# Main.net
KiCad netlist of a schematic drawn in Altium Designer
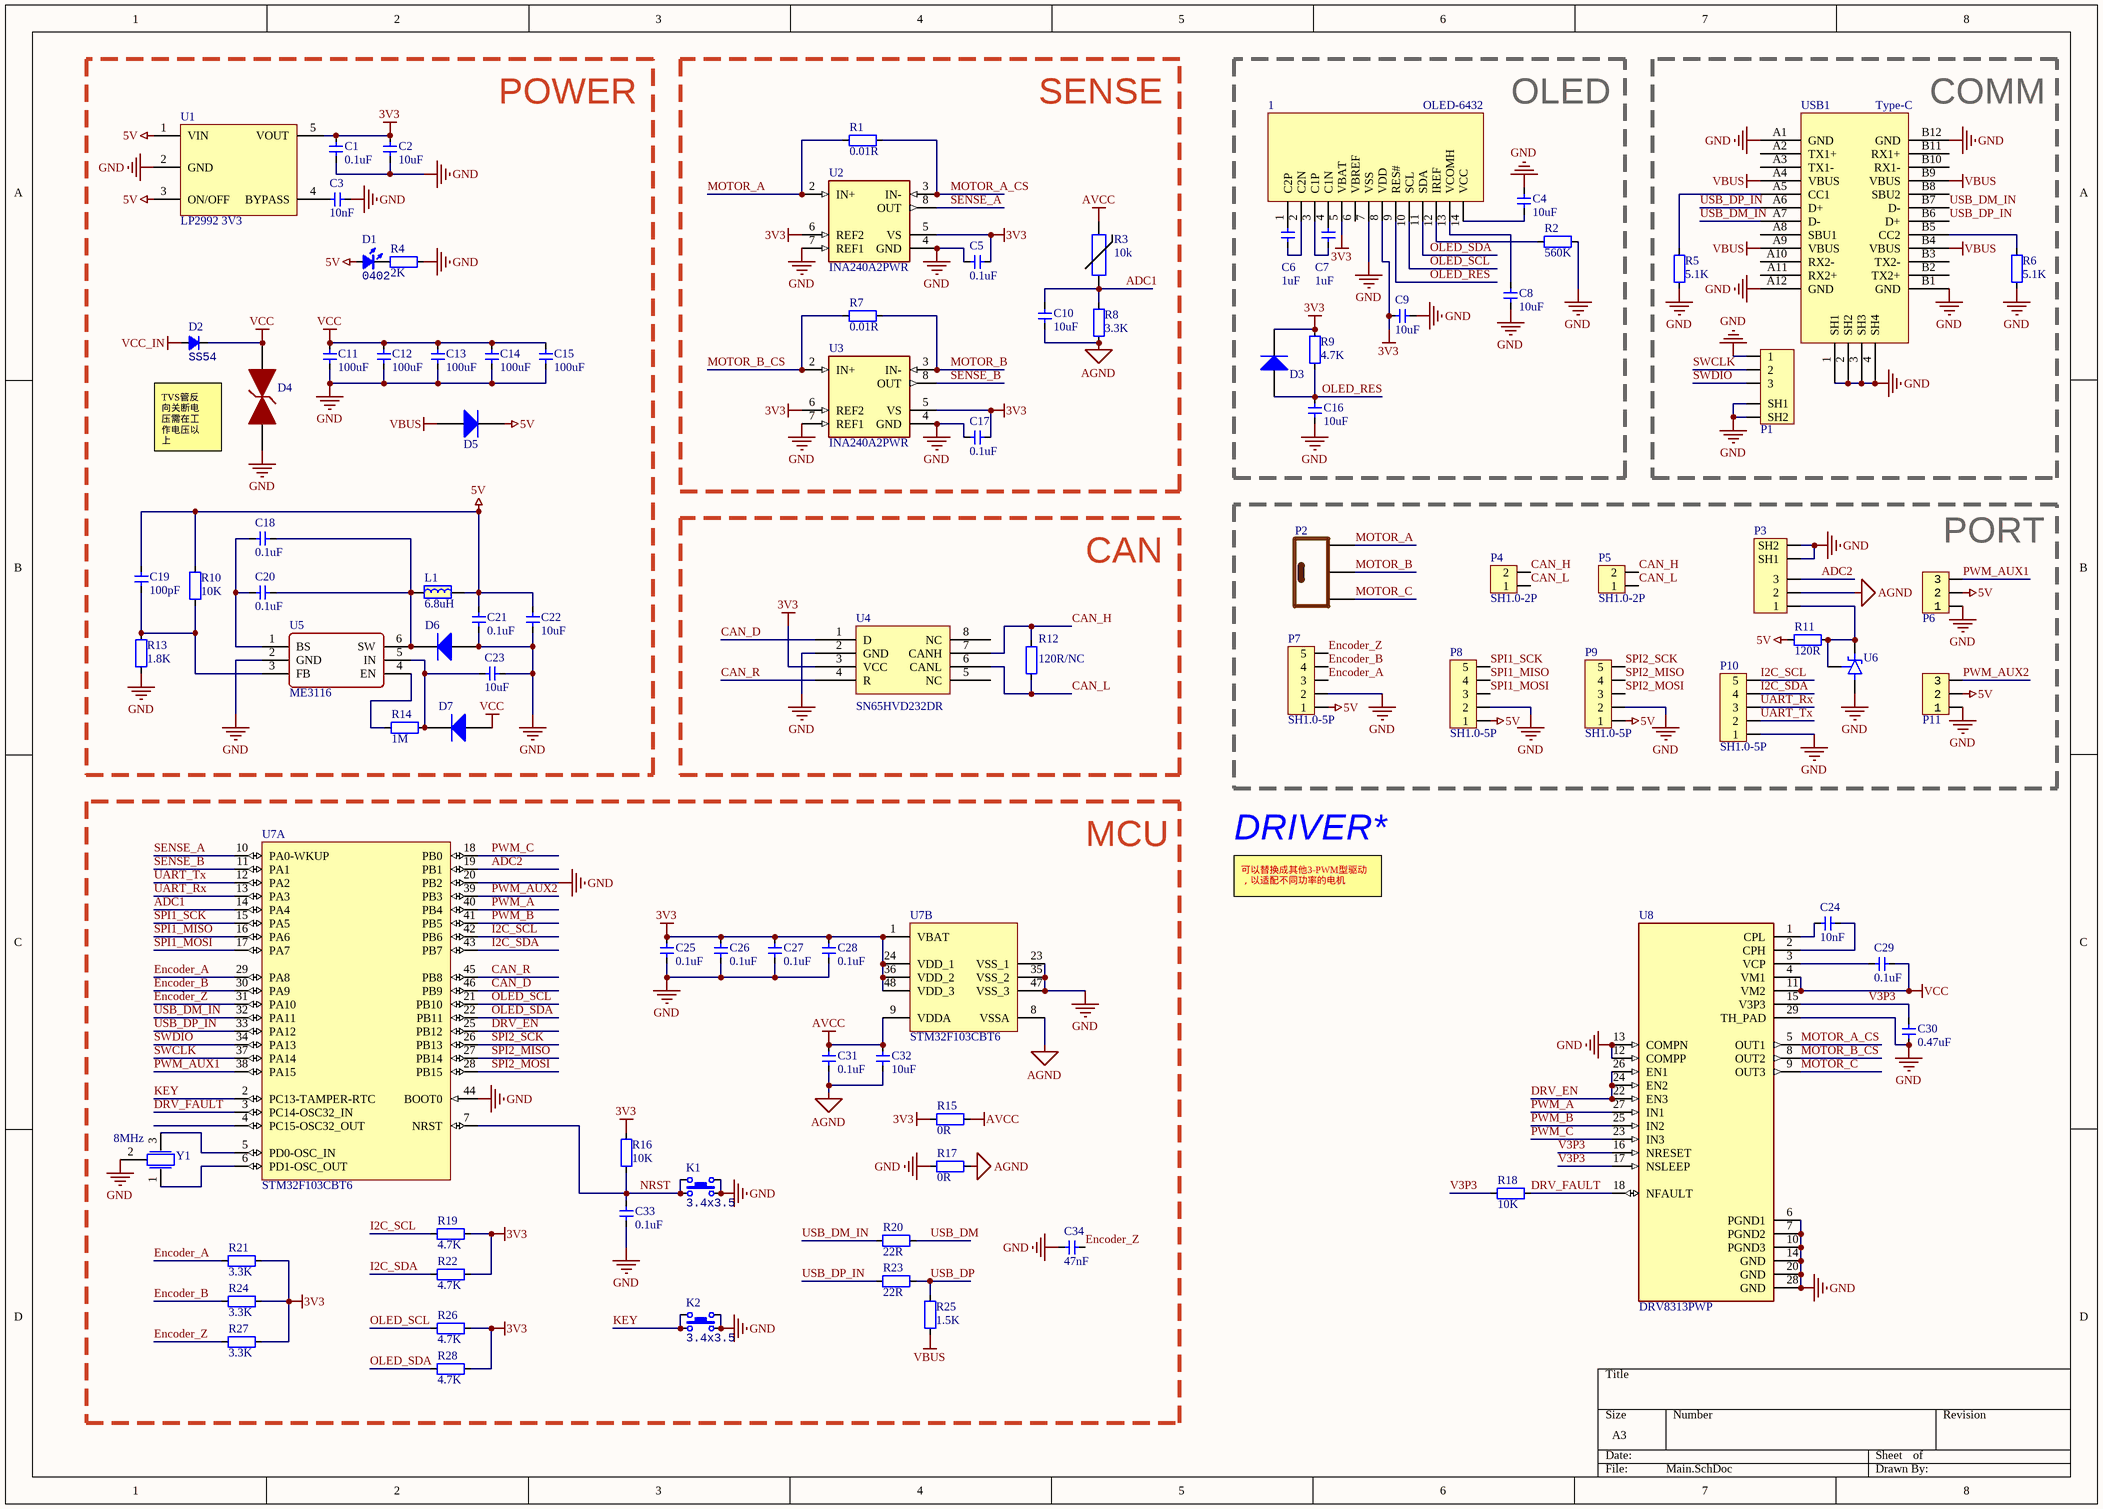
[diagram p0: Main.SchDoc]

(export (version "E")
  (design (tool "Eeschema 10.0.6"))
  (components
    (comp (ref "1")
      (value "OLED-6432")
      (footprint "OLED-6432-TOP")
      (description "显示屏")
      (libsource (lib "mLib") (part "OLED-6432"))
    )
    (comp (ref "C1")
      (value "0.1uF")
      (footprint "CAP_0402")
      (description "Capacitor")
      (libsource (lib "MyPcbLib") (part "电容-0402"))
    )
    (comp (ref "C2")
      (value "10uF")
      (footprint "CAP_0402")
      (description "Capacitor")
      (libsource (lib "MyPcbLib") (part "电容-0402"))
    )
    (comp (ref "C3")
      (value "10nF")
      (footprint "CAP_0402")
      (description "Capacitor")
      (libsource (lib "MyPcbLib") (part "电容-0402"))
    )
    (comp (ref "C4")
      (value "10uF")
      (footprint "CAP_0402")
      (description "Capacitor")
      (libsource (lib "MyPcbLib") (part "电容-0402"))
    )
    (comp (ref "C5")
      (value "0.1uF")
      (footprint "CAP_0402")
      (description "Capacitor")
      (libsource (lib "MyPcbLib") (part "电容-0402"))
    )
    (comp (ref "C6")
      (value "1uF")
      (footprint "CAP_0402")
      (description "Capacitor")
      (libsource (lib "MyPcbLib") (part "电容-0402"))
    )
    (comp (ref "C7")
      (value "1uF")
      (footprint "CAP_0402")
      (description "Capacitor")
      (libsource (lib "MyPcbLib") (part "电容-0402"))
    )
    (comp (ref "C8")
      (value "10uF")
      (footprint "CAP_0402")
      (description "Capacitor")
      (libsource (lib "MyPcbLib") (part "电容-0402"))
    )
    (comp (ref "C9")
      (value "10uF")
      (footprint "CAP_0402")
      (description "Capacitor")
      (libsource (lib "MyPcbLib") (part "电容-0402"))
    )
    (comp (ref "C10")
      (value "10uF")
      (footprint "CAP_0402")
      (description "Capacitor")
      (libsource (lib "MyPcbLib") (part "电容-0402"))
    )
    (comp (ref "C11")
      (value "100uF")
      (footprint "1206-CAP")
      (description "Capacitor")
      (libsource (lib "MyPcbLib") (part "电容-1206"))
    )
    (comp (ref "C12")
      (value "100uF")
      (footprint "1206-CAP")
      (description "Capacitor")
      (libsource (lib "MyPcbLib") (part "电容-1206"))
    )
    (comp (ref "C13")
      (value "100uF")
      (footprint "1206-CAP")
      (description "Capacitor")
      (libsource (lib "MyPcbLib") (part "电容-1206"))
    )
    (comp (ref "C14")
      (value "100uF")
      (footprint "1206-CAP")
      (description "Capacitor")
      (libsource (lib "MyPcbLib") (part "电容-1206"))
    )
    (comp (ref "C15")
      (value "100uF")
      (footprint "1206-CAP")
      (description "Capacitor")
      (libsource (lib "MyPcbLib") (part "电容-1206"))
    )
    (comp (ref "C16")
      (value "10uF")
      (footprint "CAP_0402")
      (description "Capacitor")
      (libsource (lib "MyPcbLib") (part "电容-0402"))
    )
    (comp (ref "C17")
      (value "0.1uF")
      (footprint "CAP_0402")
      (description "Capacitor")
      (libsource (lib "MyPcbLib") (part "电容-0402"))
    )
    (comp (ref "C18")
      (value "0.1uF")
      (footprint "CAP_0402")
      (description "Capacitor")
      (libsource (lib "MyPcbLib") (part "电容-0402"))
    )
    (comp (ref "C19")
      (value "100pF")
      (footprint "CAP_0402")
      (description "Capacitor")
      (libsource (lib "MyPcbLib") (part "电容-0402"))
    )
    (comp (ref "C20")
      (value "0.1uF")
      (footprint "CAP_0402")
      (description "Capacitor")
      (libsource (lib "MyPcbLib") (part "电容-0402"))
    )
    (comp (ref "C21")
      (value "0.1uF")
      (footprint "CAP_0402")
      (description "Capacitor")
      (libsource (lib "MyPcbLib") (part "电容-0402"))
    )
    (comp (ref "C22")
      (value "10uF")
      (footprint "CAP_0402")
      (description "Capacitor")
      (libsource (lib "MyPcbLib") (part "电容-0402"))
    )
    (comp (ref "C23")
      (value "10uF")
      (footprint "CAP_0402")
      (description "Capacitor")
      (libsource (lib "MyPcbLib") (part "电容-0402"))
    )
    (comp (ref "C24")
      (value "10nF")
      (footprint "CAP_0402")
      (description "Capacitor")
      (libsource (lib "MyPcbLib") (part "电容-0402"))
    )
    (comp (ref "C25")
      (value "0.1uF")
      (footprint "CAP_0402")
      (description "Capacitor")
      (libsource (lib "MyPcbLib") (part "电容-0402"))
    )
    (comp (ref "C26")
      (value "0.1uF")
      (footprint "CAP_0402")
      (description "Capacitor")
      (libsource (lib "MyPcbLib") (part "电容-0402"))
    )
    (comp (ref "C27")
      (value "0.1uF")
      (footprint "CAP_0402")
      (description "Capacitor")
      (libsource (lib "MyPcbLib") (part "电容-0402"))
    )
    (comp (ref "C28")
      (value "0.1uF")
      (footprint "CAP_0402")
      (description "Capacitor")
      (libsource (lib "MyPcbLib") (part "电容-0402"))
    )
    (comp (ref "C29")
      (value "0.1uF")
      (footprint "CAP_0402")
      (description "Capacitor")
      (libsource (lib "MyPcbLib") (part "电容-0402"))
    )
    (comp (ref "C30")
      (value "0.47uF")
      (footprint "CAP_0402")
      (description "Capacitor")
      (libsource (lib "MyPcbLib") (part "电容-0402"))
    )
    (comp (ref "C31")
      (value "0.1uF")
      (footprint "CAP_0402")
      (description "Capacitor")
      (libsource (lib "MyPcbLib") (part "电容-0402"))
    )
    (comp (ref "C32")
      (value "10uF")
      (footprint "CAP_0402")
      (description "Capacitor")
      (libsource (lib "MyPcbLib") (part "电容-0402"))
    )
    (comp (ref "C33")
      (value "0.1uF")
      (footprint "CAP_0402")
      (description "Capacitor")
      (libsource (lib "MyPcbLib") (part "电容-0402"))
    )
    (comp (ref "C34")
      (value "47nF")
      (footprint "CAP_0402")
      (description "Capacitor")
      (libsource (lib "MyPcbLib") (part "电容-0402"))
    )
    (comp (ref "D1")
      (value "color?")
      (footprint "LED_0402_RED")
      (description "LED")
      (fields (field (name "TYPE") "0402"))
      (libsource (lib "KitSprout") (part "LED_0402"))
    )
    (comp (ref "D2")
      (value "SS54")
      (footprint "DO-214AC")
      (description "Diode")
      (libsource (lib "KitSprout") (part "Diode_SMA"))
    )
    (comp (ref "D3")
      (value "二极管-5B5817WS")
      (footprint "SOD-323")
      (description "40V")
      (libsource (lib "MyPcbLib") (part "二极管-5B5817WS"))
    )
    (comp (ref "D4")
      (value "SMBJ28CA")
      (footprint "SMBJ-CA_MFG")
      (libsource (lib "MyPcbLib") (part "SMBJ28CA"))
    )
    (comp (ref "D5")
      (value "二极管-5B5819WS")
      (footprint "SOD-323")
      (description "40V")
      (libsource (lib "MyPcbLib") (part "二极管-5B5817WS"))
    )
    (comp (ref "D6")
      (value "二极管-5B5819WS")
      (footprint "SOD-323")
      (description "40V")
      (libsource (lib "MyPcbLib") (part "二极管-5B5817WS"))
    )
    (comp (ref "D7")
      (value "二极管-5B5819WS")
      (footprint "SOD-323")
      (description "40V")
      (libsource (lib "MyPcbLib") (part "二极管-5B5817WS"))
    )
    (comp (ref "K1")
      (value "3.4x3.5")
      (footprint "ButtonTACT_3.5*3.55_90")
      (description "Button")
      (fields (field (name "Comment") "TACT 4P"))
      (libsource (lib "KitSprout") (part "ButtonTACT"))
    )
    (comp (ref "K2")
      (value "3.4x3.5")
      (footprint "ButtonTACT_3.5*3.55_90")
      (description "Button")
      (fields (field (name "Comment") "TACT 4P"))
      (libsource (lib "KitSprout") (part "ButtonTACT"))
    )
    (comp (ref "L1") (value "6.8uH") (footprint "IND-201612") (libsource (lib "MyPcbLib") (part "电感-201612")))
    (comp (ref "P1")
      (value "SH1.0-3P")
      (footprint "SH1.0-3P")
      (description "Header")
      (libsource (lib "") (part "SH1.0-3P_1"))
    )
    (comp (ref "P2")
      (value "电机接插件-3P")
      (footprint "AMASS-MR30-M")
      (description "AMASS MR30")
      (libsource (lib "MyPcbLib") (part "电机接插件-3P"))
    )
    (comp (ref "P3")
      (value "SH1.0-3P")
      (footprint "SH1.0-3P")
      (description "Header")
      (libsource (lib "MyPcbLib") (part "SH1.0-3P"))
    )
    (comp (ref "P4") (value "SH1.0-2P") (footprint "SH1.0-2P") (libsource (lib "MyPcbLib") (part "SH1.0-2P")))
    (comp (ref "P5") (value "SH1.0-2P") (footprint "SH1.0-2P") (libsource (lib "MyPcbLib") (part "SH1.0-2P")))
    (comp (ref "P6")
      (value "HDR1x3_2.54")
      (footprint "HDR1X3_2.54_180")
      (description "Header")
      (libsource (lib "KitSprout") (part "HDR1x3_2.54"))
    )
    (comp (ref "P7") (value "SH1.0-5P") (footprint "SH1.0-5P") (libsource (lib "MyPcbLib") (part "SH1.0-5P")))
    (comp (ref "P8") (value "SH1.0-5P") (footprint "SH1.0-5P") (libsource (lib "MyPcbLib") (part "SH1.0-5P")))
    (comp (ref "P9") (value "SH1.0-5P") (footprint "SH1.0-5P") (libsource (lib "MyPcbLib") (part "SH1.0-5P")))
    (comp (ref "P10")
      (value "SH1.0-5P")
      (footprint "SH1.0-5P")
      (libsource (lib "MyPcbLib") (part "SH1.0-5P"))
    )
    (comp (ref "P11")
      (value "HDR1x3_2.54")
      (footprint "HDR1X3_2.54_180")
      (description "Header")
      (libsource (lib "KitSprout") (part "HDR1x3_2.54"))
    )
    (comp (ref "R1")
      (value "0.01R")
      (footprint "1206-RES")
      (description "Resistor")
      (libsource (lib "MyPcbLib") (part "电阻-1206"))
    )
    (comp (ref "R2")
      (value "560K")
      (footprint "RES_0402")
      (description "Resistor")
      (libsource (lib "") (part "电阻-0402_2"))
    )
    (comp (ref "R3")
      (value "10k")
      (footprint "RES_0402")
      (description "THERMISTOR 10K OHM NTC 0402 SMD")
      (fields (field (name "Comment") "NCP15XH103F03RC"))
      (libsource (lib "MyPcbLib") (part "NCP15XH103F03RC"))
    )
    (comp (ref "R4")
      (value "2K")
      (footprint "RES_0402")
      (description "Resistor")
      (libsource (lib "") (part "电阻-0402_2"))
    )
    (comp (ref "R5")
      (value "5.1K")
      (footprint "RES_0402")
      (description "Resistor")
      (libsource (lib "") (part "电阻-0402_3"))
    )
    (comp (ref "R6")
      (value "5.1K")
      (footprint "RES_0402")
      (description "Resistor")
      (libsource (lib "") (part "电阻-0402_3"))
    )
    (comp (ref "R7")
      (value "0.01R")
      (footprint "1206-RES")
      (description "Resistor")
      (libsource (lib "MyPcbLib") (part "电阻-1206"))
    )
    (comp (ref "R8")
      (value "3.3K")
      (footprint "RES_0402")
      (description "Resistor")
      (libsource (lib "") (part "电阻-0402_1"))
    )
    (comp (ref "R9")
      (value "4.7K")
      (footprint "RES_0402")
      (description "Resistor")
      (libsource (lib "") (part "电阻-0402_3"))
    )
    (comp (ref "R10")
      (value "10K")
      (footprint "RES_0402")
      (description "Resistor")
      (libsource (lib "") (part "电阻-0402_1"))
    )
    (comp (ref "R11")
      (value "120R")
      (footprint "RES_0402")
      (description "Resistor")
      (libsource (lib "MyPcbLib") (part "电阻-0402"))
    )
    (comp (ref "R12")
      (value "120R/NC")
      (footprint "RES_0402")
      (description "Resistor")
      (libsource (lib "") (part "电阻-0402_3"))
    )
    (comp (ref "R13")
      (value "1.8K")
      (footprint "RES_0402")
      (description "Resistor")
      (libsource (lib "") (part "电阻-0402_1"))
    )
    (comp (ref "R14")
      (value "1M")
      (footprint "RES_0402")
      (description "Resistor")
      (libsource (lib "") (part "电阻-0402_2"))
    )
    (comp (ref "R15")
      (value "0R")
      (footprint "RES_0402")
      (description "Resistor")
      (libsource (lib "") (part "电阻-0402_2"))
    )
    (comp (ref "R16")
      (value "10K")
      (footprint "RES_0402")
      (description "Resistor")
      (libsource (lib "") (part "电阻-0402_1"))
    )
    (comp (ref "R17")
      (value "0R")
      (footprint "RES_0402")
      (description "Resistor")
      (libsource (lib "") (part "电阻-0402_2"))
    )
    (comp (ref "R18")
      (value "10K")
      (footprint "RES_0402")
      (description "Resistor")
      (libsource (lib "MyPcbLib") (part "电阻-0402"))
    )
    (comp (ref "R19")
      (value "4.7K")
      (footprint "RES_0402")
      (description "Resistor")
      (libsource (lib "MyPcbLib") (part "电阻-0402"))
    )
    (comp (ref "R20")
      (value "22R")
      (footprint "RES_0402")
      (description "Resistor")
      (libsource (lib "") (part "电阻-0402_2"))
    )
    (comp (ref "R21")
      (value "3.3K")
      (footprint "RES_0402")
      (description "Resistor")
      (libsource (lib "") (part "电阻-0402_2"))
    )
    (comp (ref "R22")
      (value "4.7K")
      (footprint "RES_0402")
      (description "Resistor")
      (libsource (lib "MyPcbLib") (part "电阻-0402"))
    )
    (comp (ref "R23")
      (value "22R")
      (footprint "RES_0402")
      (description "Resistor")
      (libsource (lib "") (part "电阻-0402_2"))
    )
    (comp (ref "R24")
      (value "3.3K")
      (footprint "RES_0402")
      (description "Resistor")
      (libsource (lib "") (part "电阻-0402_2"))
    )
    (comp (ref "R25")
      (value "1.5K")
      (footprint "RES_0402")
      (description "Resistor")
      (libsource (lib "") (part "电阻-0402_3"))
    )
    (comp (ref "R26")
      (value "4.7K")
      (footprint "RES_0402")
      (description "Resistor")
      (libsource (lib "MyPcbLib") (part "电阻-0402"))
    )
    (comp (ref "R27")
      (value "3.3K")
      (footprint "RES_0402")
      (description "Resistor")
      (libsource (lib "") (part "电阻-0402_2"))
    )
    (comp (ref "R28")
      (value "4.7K")
      (footprint "RES_0402")
      (description "Resistor")
      (libsource (lib "MyPcbLib") (part "电阻-0402"))
    )
    (comp (ref "U1")
      (value "LP2992 3V3")
      (footprint "SOT23-5")
      (description "LDO")
      (libsource (lib "MyPcbLib") (part "LP2992"))
    )
    (comp (ref "U2")
      (value "INA240A2PWR")
      (footprint "SOP65 P640X120-8N")
      (fields (field (name "MF") "Texas Instruments"))
      (libsource (lib "mLib") (part "INA240A2PWR"))
    )
    (comp (ref "U3")
      (value "INA240A2PWR")
      (footprint "SOP65 P640X120-8N")
      (fields (field (name "MF") "Texas Instruments"))
      (libsource (lib "mLib") (part "INA240A2PWR"))
    )
    (comp (ref "U4")
      (value "SN65HVD232D")
      (footprint "SO-8")
      (fields
        (field (name "MANUFACTURER") "Texas Instruments")
        (field (name "MANUFACTURER PART NUMBER") "SN65HVD232DR")
      )
      (libsource (lib "MyPcbLib") (part "SN65HVD232D"))
    )
    (comp (ref "U5")
      (value "ME3116")
      (footprint "SOT23-6")
      (description "DC-DC")
      (libsource (lib "MyPcbLib") (part "ME3116"))
    )
    (comp (ref "U6")
      (value "TL431IDBZT")
      (footprint "SOT23-3")
      (description "Adjustable precision shunt regulator 3-SOT-23 -40 to 85")
      (fields (field (name "MF") "Texas Instruments"))
      (libsource (lib "MyPcbLib") (part "TL431IDBZT"))
    )
    (comp (ref "U7")
      (value "STM32F103CBT6")
      (footprint "LQFP-48")
      (libsource (lib "STMicroelectronics STM32 F1") (part "STM32F103CBT6"))
    )
    (comp (ref "U8")
      (value "DRV8313PWP")
      (footprint "HTSSOP-28")
      (description "65-V max, 3-A peak 3-phase motor driver 28-HTSSOP -40 to 125")
      (fields (field (name "MF") "Texas Instruments"))
      (libsource (lib "MyPcbLib") (part "DRV8313PWP"))
    )
    (comp (ref "USB1")
      (value "Type-C")
      (footprint "Type-C-TOP")
      (libsource (lib "MyPcbLib") (part "USB-Type-C-TOP"))
    )
    (comp (ref "Y1")
      (value "8MHz")
      (footprint "晶振-3P")
      (description "村田贴片")
      (libsource (lib "MyPcbLib") (part "晶振-3Pin"))
    )
  )
  (nets
    (net (code "1") (name "/ADC1") (class "Default")
      (node (ref "C10") (pin "2") (pinfunction "2_2") (pintype "passive"))
      (node (ref "R3") (pin "1") (pinfunction "0_1") (pintype "passive"))
      (node (ref "R8") (pin "2") (pinfunction "2_2") (pintype "passive"))
      (node (ref "U7") (pin "14") (pinfunction "PA4_14") (pintype "bidirectional"))
    )
    (net (code "2") (name "/ADC2") (class "Default")
      (node (ref "P3") (pin "3") (pinfunction "3_3") (pintype "passive"))
      (node (ref "U7") (pin "19") (pinfunction "PB1_19") (pintype "bidirectional"))
    )
    (net (code "3") (name "/CAN_D") (class "Default")
      (node (ref "U4") (pin "1") (pinfunction "D_1") (pintype "passive"))
      (node (ref "U7") (pin "46") (pinfunction "PB9_46") (pintype "bidirectional"))
    )
    (net (code "4") (name "/CAN_H") (class "Default")
      (node (ref "P4") (pin "2") (pinfunction "2_2") (pintype "passive"))
      (node (ref "P5") (pin "2") (pinfunction "2_2") (pintype "passive"))
      (node (ref "R12") (pin "1") (pinfunction "1_1") (pintype "passive"))
      (node (ref "U4") (pin "7") (pinfunction "CANH_7") (pintype "passive"))
    )
    (net (code "5") (name "/CAN_L") (class "Default")
      (node (ref "P4") (pin "1") (pinfunction "1_1") (pintype "passive"))
      (node (ref "P5") (pin "1") (pinfunction "1_1") (pintype "passive"))
      (node (ref "R12") (pin "2") (pinfunction "2_2") (pintype "passive"))
      (node (ref "U4") (pin "6") (pinfunction "CANL_6") (pintype "passive"))
    )
    (net (code "6") (name "/CAN_R") (class "Default")
      (node (ref "U4") (pin "4") (pinfunction "R_4") (pintype "passive"))
      (node (ref "U7") (pin "45") (pinfunction "PB8_45") (pintype "bidirectional"))
    )
    (net (code "7") (name "/DRV_EN") (class "Default")
      (node (ref "U7") (pin "25") (pinfunction "PB12_25") (pintype "bidirectional"))
      (node (ref "U8") (pin "22") (pinfunction "EN3_22") (pintype "input"))
      (node (ref "U8") (pin "24") (pinfunction "EN2_24") (pintype "input"))
      (node (ref "U8") (pin "26") (pinfunction "EN1_26") (pintype "input"))
    )
    (net (code "8") (name "/DRV_FAULT") (class "Default")
      (node (ref "R18") (pin "2") (pinfunction "2_2") (pintype "passive"))
      (node (ref "U7") (pin "3") (pinfunction "PC14-OSC32_IN_3") (pintype "bidirectional"))
      (node (ref "U8") (pin "18") (pinfunction "NFAULT_18") (pintype "bidirectional"))
    )
    (net (code "9") (name "/Encoder_A") (class "Default")
      (node (ref "P7") (pin "3") (pinfunction "3_3") (pintype "passive"))
      (node (ref "R21") (pin "2") (pinfunction "2_2") (pintype "passive"))
      (node (ref "U7") (pin "29") (pinfunction "PA8_29") (pintype "bidirectional"))
    )
    (net (code "10") (name "/Encoder_B") (class "Default")
      (node (ref "P7") (pin "4") (pinfunction "4_4") (pintype "passive"))
      (node (ref "R24") (pin "2") (pinfunction "2_2") (pintype "passive"))
      (node (ref "U7") (pin "30") (pinfunction "PA9_30") (pintype "bidirectional"))
    )
    (net (code "11") (name "/Encoder_Z") (class "Default")
      (node (ref "C34") (pin "1") (pinfunction "1_1") (pintype "passive"))
      (node (ref "P7") (pin "5") (pinfunction "5_5") (pintype "passive"))
      (node (ref "R27") (pin "2") (pinfunction "2_2") (pintype "passive"))
      (node (ref "U7") (pin "31") (pinfunction "PA10_31") (pintype "bidirectional"))
    )
    (net (code "12") (name "/I2C_SCL") (class "Default")
      (node (ref "P10") (pin "5") (pinfunction "5_5") (pintype "passive"))
      (node (ref "R19") (pin "1") (pinfunction "1_1") (pintype "passive"))
      (node (ref "U7") (pin "42") (pinfunction "PB6_42") (pintype "bidirectional"))
    )
    (net (code "13") (name "/I2C_SDA") (class "Default")
      (node (ref "P10") (pin "4") (pinfunction "4_4") (pintype "passive"))
      (node (ref "R22") (pin "1") (pinfunction "1_1") (pintype "passive"))
      (node (ref "U7") (pin "43") (pinfunction "PB7_43") (pintype "bidirectional"))
    )
    (net (code "14") (name "/KEY") (class "Default")
      (node (ref "K2") (pin "1") (pinfunction "1_1") (pintype "passive"))
      (node (ref "K2") (pin "3") (pinfunction "3_3") (pintype "passive"))
      (node (ref "U7") (pin "2") (pinfunction "PC13-TAMPER-RTC_2") (pintype "bidirectional"))
    )
    (net (code "15") (name "/MOTOR_A") (class "Default")
      (node (ref "P2") (pin "3") (pinfunction "3_3") (pintype "passive"))
      (node (ref "R1") (pin "1") (pinfunction "1_1") (pintype "passive"))
      (node (ref "U2") (pin "2") (pinfunction "IN+_2") (pintype "input"))
    )
    (net (code "16") (name "/MOTOR_A_CS") (class "Default")
      (node (ref "R1") (pin "2") (pinfunction "2_2") (pintype "passive"))
      (node (ref "U2") (pin "3") (pinfunction "IN-_3") (pintype "input"))
      (node (ref "U8") (pin "5") (pinfunction "OUT1_5") (pintype "output"))
    )
    (net (code "17") (name "/MOTOR_B") (class "Default")
      (node (ref "P2") (pin "2") (pinfunction "2_2") (pintype "passive"))
      (node (ref "R7") (pin "2") (pinfunction "2_2") (pintype "passive"))
      (node (ref "U3") (pin "3") (pinfunction "IN-_3") (pintype "input"))
    )
    (net (code "18") (name "/MOTOR_B_CS") (class "Default")
      (node (ref "R7") (pin "1") (pinfunction "1_1") (pintype "passive"))
      (node (ref "U3") (pin "2") (pinfunction "IN+_2") (pintype "input"))
      (node (ref "U8") (pin "8") (pinfunction "OUT2_8") (pintype "output"))
    )
    (net (code "19") (name "/MOTOR_C") (class "Default")
      (node (ref "P2") (pin "1") (pinfunction "1_1") (pintype "passive"))
      (node (ref "U8") (pin "9") (pinfunction "OUT3_9") (pintype "output"))
    )
    (net (code "20") (name "/NRST") (class "Default")
      (node (ref "C33") (pin "2") (pinfunction "2_2") (pintype "passive"))
      (node (ref "K1") (pin "1") (pinfunction "1_1") (pintype "passive"))
      (node (ref "K1") (pin "3") (pinfunction "3_3") (pintype "passive"))
      (node (ref "R16") (pin "1") (pinfunction "1_1") (pintype "passive"))
      (node (ref "U7") (pin "7") (pinfunction "NRST_7") (pintype "bidirectional"))
    )
    (net (code "21") (name "/OLED_RES") (class "Default")
      (node (ref "1") (pin "9") (pinfunction "RES#_9") (pintype "passive"))
      (node (ref "C16") (pin "2") (pinfunction "2_2") (pintype "passive"))
      (node (ref "D3") (pin "1") (pinfunction "A_1") (pintype "passive"))
      (node (ref "R9") (pin "2") (pinfunction "2_2") (pintype "passive"))
    )
    (net (code "22") (name "/OLED_SCL") (class "Default")
      (node (ref "1") (pin "10") (pinfunction "SCL_10") (pintype "passive"))
      (node (ref "R26") (pin "1") (pinfunction "1_1") (pintype "passive"))
      (node (ref "U7") (pin "21") (pinfunction "PB10_21") (pintype "bidirectional"))
    )
    (net (code "23") (name "/OLED_SDA") (class "Default")
      (node (ref "1") (pin "11") (pinfunction "SDA_11") (pintype "passive"))
      (node (ref "R28") (pin "1") (pinfunction "1_1") (pintype "passive"))
      (node (ref "U7") (pin "22") (pinfunction "PB11_22") (pintype "bidirectional"))
    )
    (net (code "24") (name "/PWM_A") (class "Default")
      (node (ref "U7") (pin "40") (pinfunction "PB4_40") (pintype "bidirectional"))
      (node (ref "U8") (pin "27") (pinfunction "IN1_27") (pintype "input"))
    )
    (net (code "25") (name "/PWM_AUX1") (class "Default")
      (node (ref "P6") (pin "3") (pinfunction "3_3") (pintype "passive"))
      (node (ref "U7") (pin "38") (pinfunction "PA15_38") (pintype "bidirectional"))
    )
    (net (code "26") (name "/PWM_AUX2") (class "Default")
      (node (ref "P11") (pin "3") (pinfunction "3_3") (pintype "passive"))
      (node (ref "U7") (pin "39") (pinfunction "PB3_39") (pintype "bidirectional"))
    )
    (net (code "27") (name "/PWM_B") (class "Default")
      (node (ref "U7") (pin "41") (pinfunction "PB5_41") (pintype "bidirectional"))
      (node (ref "U8") (pin "25") (pinfunction "IN2_25") (pintype "input"))
    )
    (net (code "28") (name "/PWM_C") (class "Default")
      (node (ref "U7") (pin "18") (pinfunction "PB0_18") (pintype "bidirectional"))
      (node (ref "U8") (pin "23") (pinfunction "IN3_23") (pintype "input"))
    )
    (net (code "29") (name "/SENSE_A") (class "Default")
      (node (ref "U2") (pin "8") (pinfunction "OUT_8") (pintype "output"))
      (node (ref "U7") (pin "10") (pinfunction "PA0-WKUP_10") (pintype "bidirectional"))
    )
    (net (code "30") (name "/SENSE_B") (class "Default")
      (node (ref "U3") (pin "8") (pinfunction "OUT_8") (pintype "output"))
      (node (ref "U7") (pin "11") (pinfunction "PA1_11") (pintype "bidirectional"))
    )
    (net (code "31") (name "/SPI1_MISO") (class "Default")
      (node (ref "P8") (pin "4") (pinfunction "4_4") (pintype "passive"))
      (node (ref "U7") (pin "16") (pinfunction "PA6_16") (pintype "bidirectional"))
    )
    (net (code "32") (name "/SPI1_MOSI") (class "Default")
      (node (ref "P8") (pin "3") (pinfunction "3_3") (pintype "passive"))
      (node (ref "U7") (pin "17") (pinfunction "PA7_17") (pintype "bidirectional"))
    )
    (net (code "33") (name "/SPI1_SCK") (class "Default")
      (node (ref "P8") (pin "5") (pinfunction "5_5") (pintype "passive"))
      (node (ref "U7") (pin "15") (pinfunction "PA5_15") (pintype "bidirectional"))
    )
    (net (code "34") (name "/SPI2_MISO") (class "Default")
      (node (ref "P9") (pin "4") (pinfunction "4_4") (pintype "passive"))
      (node (ref "U7") (pin "27") (pinfunction "PB14_27") (pintype "bidirectional"))
    )
    (net (code "35") (name "/SPI2_MOSI") (class "Default")
      (node (ref "P9") (pin "3") (pinfunction "3_3") (pintype "passive"))
      (node (ref "U7") (pin "28") (pinfunction "PB15_28") (pintype "bidirectional"))
    )
    (net (code "36") (name "/SPI2_SCK") (class "Default")
      (node (ref "P9") (pin "5") (pinfunction "5_5") (pintype "passive"))
      (node (ref "U7") (pin "26") (pinfunction "PB13_26") (pintype "bidirectional"))
    )
    (net (code "37") (name "/SWCLK") (class "Default")
      (node (ref "P1") (pin "2") (pinfunction "2_2") (pintype "passive"))
      (node (ref "U7") (pin "37") (pinfunction "PA14_37") (pintype "bidirectional"))
    )
    (net (code "38") (name "/SWDIO") (class "Default")
      (node (ref "P1") (pin "3") (pinfunction "3_3") (pintype "passive"))
      (node (ref "U7") (pin "34") (pinfunction "PA13_34") (pintype "bidirectional"))
    )
    (net (code "39") (name "/UART_Rx") (class "Default")
      (node (ref "P10") (pin "3") (pinfunction "3_3") (pintype "passive"))
      (node (ref "U7") (pin "13") (pinfunction "PA3_13") (pintype "bidirectional"))
    )
    (net (code "40") (name "/UART_Tx") (class "Default")
      (node (ref "P10") (pin "2") (pinfunction "2_2") (pintype "passive"))
      (node (ref "U7") (pin "12") (pinfunction "PA2_12") (pintype "bidirectional"))
    )
    (net (code "41") (name "/USB_DM") (class "Default")
      (node (ref "R20") (pin "1") (pinfunction "1_1") (pintype "passive"))
    )
    (net (code "42") (name "/USB_DM_IN") (class "Default")
      (node (ref "R20") (pin "2") (pinfunction "2_2") (pintype "passive"))
      (node (ref "U7") (pin "32") (pinfunction "PA11_32") (pintype "bidirectional"))
      (node (ref "USB1") (pin "A7") (pinfunction "D-_A7") (pintype "passive"))
      (node (ref "USB1") (pin "B7") (pinfunction "D-_B7") (pintype "passive"))
    )
    (net (code "43") (name "/USB_DP") (class "Default")
      (node (ref "R23") (pin "1") (pinfunction "1_1") (pintype "passive"))
      (node (ref "R25") (pin "1") (pinfunction "1_1") (pintype "passive"))
    )
    (net (code "44") (name "/USB_DP_IN") (class "Default")
      (node (ref "R23") (pin "2") (pinfunction "2_2") (pintype "passive"))
      (node (ref "U7") (pin "33") (pinfunction "PA12_33") (pintype "bidirectional"))
      (node (ref "USB1") (pin "A6") (pinfunction "D+_A6") (pintype "passive"))
      (node (ref "USB1") (pin "B6") (pinfunction "D+_B6") (pintype "passive"))
    )
    (net (code "45") (name "/V3P3") (class "Default")
      (node (ref "C30") (pin "2") (pinfunction "2_2") (pintype "passive"))
      (node (ref "R18") (pin "1") (pinfunction "1_1") (pintype "passive"))
      (node (ref "U8") (pin "15") (pinfunction "V3P3_15") (pintype "power_in"))
      (node (ref "U8") (pin "16") (pinfunction "NRESET_16") (pintype "input"))
      (node (ref "U8") (pin "17") (pinfunction "NSLEEP_17") (pintype "input"))
    )
    (net (code "46") (name "3V3") (class "Default")
      (node (ref "1") (pin "5") (pinfunction "VBAT_5") (pintype "passive"))
      (node (ref "1") (pin "8") (pinfunction "VDD_8") (pintype "passive"))
      (node (ref "C1") (pin "2") (pinfunction "2_2") (pintype "passive"))
      (node (ref "C17") (pin "1") (pinfunction "1_1") (pintype "passive"))
      (node (ref "C2") (pin "2") (pinfunction "2_2") (pintype "passive"))
      (node (ref "C25") (pin "2") (pinfunction "2_2") (pintype "passive"))
      (node (ref "C26") (pin "2") (pinfunction "2_2") (pintype "passive"))
      (node (ref "C27") (pin "2") (pinfunction "2_2") (pintype "passive"))
      (node (ref "C28") (pin "2") (pinfunction "2_2") (pintype "passive"))
      (node (ref "C5") (pin "1") (pinfunction "1_1") (pintype "passive"))
      (node (ref "C9") (pin "2") (pinfunction "2_2") (pintype "passive"))
      (node (ref "D3") (pin "2") (pinfunction "K_2") (pintype "passive"))
      (node (ref "R15") (pin "2") (pinfunction "2_2") (pintype "passive"))
      (node (ref "R16") (pin "2") (pinfunction "2_2") (pintype "passive"))
      (node (ref "R19") (pin "2") (pinfunction "2_2") (pintype "passive"))
      (node (ref "R21") (pin "1") (pinfunction "1_1") (pintype "passive"))
      (node (ref "R22") (pin "2") (pinfunction "2_2") (pintype "passive"))
      (node (ref "R24") (pin "1") (pinfunction "1_1") (pintype "passive"))
      (node (ref "R26") (pin "2") (pinfunction "2_2") (pintype "passive"))
      (node (ref "R27") (pin "1") (pinfunction "1_1") (pintype "passive"))
      (node (ref "R28") (pin "2") (pinfunction "2_2") (pintype "passive"))
      (node (ref "R9") (pin "1") (pinfunction "1_1") (pintype "passive"))
      (node (ref "U1") (pin "5") (pinfunction "VOUT_5") (pintype "passive"))
      (node (ref "U2") (pin "5") (pinfunction "VS_5") (pintype "power_in"))
      (node (ref "U2") (pin "6") (pinfunction "REF2_6") (pintype "input"))
      (node (ref "U3") (pin "5") (pinfunction "VS_5") (pintype "power_in"))
      (node (ref "U3") (pin "6") (pinfunction "REF2_6") (pintype "input"))
      (node (ref "U4") (pin "3") (pinfunction "VCC_3") (pintype "passive"))
      (node (ref "U7") (pin "1") (pinfunction "VBAT_1") (pintype "power_in"))
      (node (ref "U7") (pin "24") (pinfunction "VDD_1_24") (pintype "power_in"))
      (node (ref "U7") (pin "36") (pinfunction "VDD_2_36") (pintype "power_in"))
      (node (ref "U7") (pin "48") (pinfunction "VDD_3_48") (pintype "power_in"))
    )
    (net (code "47") (name "5V") (class "Default")
      (node (ref "C19") (pin "1") (pinfunction "1_1") (pintype "passive"))
      (node (ref "C21") (pin "2") (pinfunction "2_2") (pintype "passive"))
      (node (ref "C22") (pin "2") (pinfunction "2_2") (pintype "passive"))
      (node (ref "D1") (pin "1") (pinfunction "A_1") (pintype "passive"))
      (node (ref "D5") (pin "2") (pinfunction "K_2") (pintype "passive"))
      (node (ref "L1") (pin "2") (pinfunction "2_2") (pintype "passive"))
      (node (ref "P11") (pin "2") (pinfunction "2_2") (pintype "passive"))
      (node (ref "P6") (pin "2") (pinfunction "2_2") (pintype "passive"))
      (node (ref "P7") (pin "1") (pinfunction "1_1") (pintype "passive"))
      (node (ref "P8") (pin "1") (pinfunction "1_1") (pintype "passive"))
      (node (ref "P9") (pin "1") (pinfunction "1_1") (pintype "passive"))
      (node (ref "R10") (pin "2") (pinfunction "2_2") (pintype "passive"))
      (node (ref "R11") (pin "1") (pinfunction "1_1") (pintype "passive"))
      (node (ref "U1") (pin "1") (pinfunction "VIN_1") (pintype "passive"))
      (node (ref "U1") (pin "3") (pinfunction "ON/OFF_3") (pintype "passive"))
    )
    (net (code "48") (name "AGND") (class "Default")
      (node (ref "C10") (pin "1") (pinfunction "1_1") (pintype "passive"))
      (node (ref "C31") (pin "1") (pinfunction "1_1") (pintype "passive"))
      (node (ref "C32") (pin "1") (pinfunction "1_1") (pintype "passive"))
      (node (ref "P3") (pin "2") (pinfunction "2_2") (pintype "passive"))
      (node (ref "R17") (pin "1") (pinfunction "1_1") (pintype "passive"))
      (node (ref "R8") (pin "1") (pinfunction "1_1") (pintype "passive"))
      (node (ref "U7") (pin "8") (pinfunction "VSSA_8") (pintype "power_in"))
    )
    (net (code "49") (name "AVCC") (class "Default")
      (node (ref "C31") (pin "2") (pinfunction "2_2") (pintype "passive"))
      (node (ref "C32") (pin "2") (pinfunction "2_2") (pintype "passive"))
      (node (ref "R15") (pin "1") (pinfunction "1_1") (pintype "passive"))
      (node (ref "R3") (pin "2") (pinfunction "0_2") (pintype "passive"))
      (node (ref "U7") (pin "9") (pinfunction "VDDA_9") (pintype "power_in"))
    )
    (net (code "50") (name "GND") (class "Default")
      (node (ref "1") (pin "7") (pinfunction "VSS_7") (pintype "passive"))
      (node (ref "C1") (pin "1") (pinfunction "1_1") (pintype "passive"))
      (node (ref "C11") (pin "1") (pinfunction "1_1") (pintype "passive"))
      (node (ref "C12") (pin "1") (pinfunction "1_1") (pintype "passive"))
      (node (ref "C13") (pin "1") (pinfunction "1_1") (pintype "passive"))
      (node (ref "C14") (pin "1") (pinfunction "1_1") (pintype "passive"))
      (node (ref "C15") (pin "1") (pinfunction "1_1") (pintype "passive"))
      (node (ref "C16") (pin "1") (pinfunction "1_1") (pintype "passive"))
      (node (ref "C17") (pin "2") (pinfunction "2_2") (pintype "passive"))
      (node (ref "C2") (pin "1") (pinfunction "1_1") (pintype "passive"))
      (node (ref "C21") (pin "1") (pinfunction "1_1") (pintype "passive"))
      (node (ref "C22") (pin "1") (pinfunction "1_1") (pintype "passive"))
      (node (ref "C23") (pin "1") (pinfunction "1_1") (pintype "passive"))
      (node (ref "C25") (pin "1") (pinfunction "1_1") (pintype "passive"))
      (node (ref "C26") (pin "1") (pinfunction "1_1") (pintype "passive"))
      (node (ref "C27") (pin "1") (pinfunction "1_1") (pintype "passive"))
      (node (ref "C28") (pin "1") (pinfunction "1_1") (pintype "passive"))
      (node (ref "C3") (pin "1") (pinfunction "1_1") (pintype "passive"))
      (node (ref "C30") (pin "1") (pinfunction "1_1") (pintype "passive"))
      (node (ref "C33") (pin "1") (pinfunction "1_1") (pintype "passive"))
      (node (ref "C34") (pin "2") (pinfunction "2_2") (pintype "passive"))
      (node (ref "C4") (pin "1") (pinfunction "1_1") (pintype "passive"))
      (node (ref "C5") (pin "2") (pinfunction "2_2") (pintype "passive"))
      (node (ref "C8") (pin "1") (pinfunction "1_1") (pintype "passive"))
      (node (ref "C9") (pin "1") (pinfunction "1_1") (pintype "passive"))
      (node (ref "D4") (pin "1") (pinfunction "1_1") (pintype "passive"))
      (node (ref "D6") (pin "1") (pinfunction "A_1") (pintype "passive"))
      (node (ref "K1") (pin "2") (pinfunction "2_2") (pintype "passive"))
      (node (ref "K1") (pin "4") (pinfunction "4_4") (pintype "passive"))
      (node (ref "K2") (pin "2") (pinfunction "2_2") (pintype "passive"))
      (node (ref "K2") (pin "4") (pinfunction "4_4") (pintype "passive"))
      (node (ref "P1") (pin "1") (pinfunction "1_1") (pintype "passive"))
      (node (ref "P1") (pin "SH1") (pinfunction "SH1_SH1") (pintype "passive"))
      (node (ref "P1") (pin "SH2") (pinfunction "SH2_SH2") (pintype "passive"))
      (node (ref "P10") (pin "1") (pinfunction "1_1") (pintype "passive"))
      (node (ref "P11") (pin "1") (pinfunction "1_1") (pintype "passive"))
      (node (ref "P3") (pin "SH1") (pinfunction "SH1_SH1") (pintype "passive"))
      (node (ref "P3") (pin "SH2") (pinfunction "SH2_SH2") (pintype "passive"))
      (node (ref "P6") (pin "1") (pinfunction "1_1") (pintype "passive"))
      (node (ref "P7") (pin "2") (pinfunction "2_2") (pintype "passive"))
      (node (ref "P8") (pin "2") (pinfunction "2_2") (pintype "passive"))
      (node (ref "P9") (pin "2") (pinfunction "2_2") (pintype "passive"))
      (node (ref "R13") (pin "1") (pinfunction "1_1") (pintype "passive"))
      (node (ref "R17") (pin "2") (pinfunction "2_2") (pintype "passive"))
      (node (ref "R2") (pin "1") (pinfunction "1_1") (pintype "passive"))
      (node (ref "R4") (pin "1") (pinfunction "1_1") (pintype "passive"))
      (node (ref "R5") (pin "2") (pinfunction "2_2") (pintype "passive"))
      (node (ref "R6") (pin "2") (pinfunction "2_2") (pintype "passive"))
      (node (ref "U1") (pin "2") (pinfunction "GND_2") (pintype "passive"))
      (node (ref "U2") (pin "4") (pinfunction "GND_4") (pintype "power_in"))
      (node (ref "U2") (pin "7") (pinfunction "REF1_7") (pintype "input"))
      (node (ref "U3") (pin "4") (pinfunction "GND_4") (pintype "power_in"))
      (node (ref "U3") (pin "7") (pinfunction "REF1_7") (pintype "input"))
      (node (ref "U4") (pin "2") (pinfunction "GND_2") (pintype "passive"))
      (node (ref "U5") (pin "2") (pinfunction "GND_2") (pintype "passive"))
      (node (ref "U6") (pin "3") (pinfunction "ANODE_3") (pintype "passive"))
      (node (ref "U7") (pin "20") (pinfunction "PB2_20") (pintype "bidirectional"))
      (node (ref "U7") (pin "23") (pinfunction "VSS_1_23") (pintype "power_in"))
      (node (ref "U7") (pin "35") (pinfunction "VSS_2_35") (pintype "power_in"))
      (node (ref "U7") (pin "44") (pinfunction "BOOT0_44") (pintype "input"))
      (node (ref "U7") (pin "47") (pinfunction "VSS_3_47") (pintype "power_in"))
      (node (ref "U8") (pin "10") (pinfunction "PGND3_10") (pintype "power_in"))
      (node (ref "U8") (pin "12") (pinfunction "COMPP_12") (pintype "input"))
      (node (ref "U8") (pin "13") (pinfunction "COMPN_13") (pintype "input"))
      (node (ref "U8") (pin "14") (pinfunction "GND_14") (pintype "power_in"))
      (node (ref "U8") (pin "20") (pinfunction "GND_20") (pintype "power_in"))
      (node (ref "U8") (pin "28") (pinfunction "GND_28") (pintype "power_in"))
      (node (ref "U8") (pin "29") (pinfunction "TH_PAD_29") (pintype "power_in"))
      (node (ref "U8") (pin "6") (pinfunction "PGND1_6") (pintype "power_in"))
      (node (ref "U8") (pin "7") (pinfunction "PGND2_7") (pintype "power_in"))
      (node (ref "USB1") (pin "1") (pinfunction "SH1_1") (pintype "passive"))
      (node (ref "USB1") (pin "2") (pinfunction "SH2_2") (pintype "passive"))
      (node (ref "USB1") (pin "3") (pinfunction "SH3_3") (pintype "passive"))
      (node (ref "USB1") (pin "4") (pinfunction "SH4_4") (pintype "passive"))
      (node (ref "USB1") (pin "A1") (pinfunction "GND_A1") (pintype "passive"))
      (node (ref "USB1") (pin "A12") (pinfunction "GND_A12") (pintype "passive"))
      (node (ref "USB1") (pin "B1") (pinfunction "GND_B1") (pintype "passive"))
      (node (ref "USB1") (pin "B12") (pinfunction "GND_B12") (pintype "passive"))
      (node (ref "Y1") (pin "2") (pinfunction "2_2") (pintype "passive"))
    )
    (net (code "51") (name "Net-(1-C1N)") (class "Default")
      (node (ref "1") (pin "4") (pinfunction "C1N_4") (pintype "passive"))
      (node (ref "C7") (pin "2") (pinfunction "2_2") (pintype "passive"))
    )
    (net (code "52") (name "Net-(1-C1P)") (class "Default")
      (node (ref "1") (pin "3") (pinfunction "C1P_3") (pintype "passive"))
      (node (ref "C7") (pin "1") (pinfunction "1_1") (pintype "passive"))
    )
    (net (code "53") (name "Net-(1-C2N)") (class "Default")
      (node (ref "1") (pin "2") (pinfunction "C2N_2") (pintype "passive"))
      (node (ref "C6") (pin "1") (pinfunction "1_1") (pintype "passive"))
    )
    (net (code "54") (name "Net-(1-C2P)") (class "Default")
      (node (ref "1") (pin "1") (pinfunction "C2P_1") (pintype "passive"))
      (node (ref "C6") (pin "2") (pinfunction "2_2") (pintype "passive"))
    )
    (net (code "55") (name "Net-(1-IREF)") (class "Default")
      (node (ref "1") (pin "12") (pinfunction "IREF_12") (pintype "passive"))
      (node (ref "R2") (pin "2") (pinfunction "2_2") (pintype "passive"))
    )
    (net (code "56") (name "Net-(1-VCC)") (class "Default")
      (node (ref "1") (pin "14") (pinfunction "VCC_14") (pintype "passive"))
      (node (ref "C4") (pin "2") (pinfunction "2_2") (pintype "passive"))
    )
    (net (code "57") (name "Net-(1-VCOMH)") (class "Default")
      (node (ref "1") (pin "13") (pinfunction "VCOMH_13") (pintype "passive"))
      (node (ref "C8") (pin "2") (pinfunction "2_2") (pintype "passive"))
    )
    (net (code "58") (name "Net-(D1-K)") (class "Default")
      (node (ref "D1") (pin "2") (pinfunction "K_2") (pintype "passive"))
      (node (ref "R4") (pin "2") (pinfunction "2_2") (pintype "passive"))
    )
    (net (code "59") (name "Net-(D6-K)") (class "Default")
      (node (ref "C18") (pin "1") (pinfunction "1_1") (pintype "passive"))
      (node (ref "C20") (pin "1") (pinfunction "1_1") (pintype "passive"))
      (node (ref "D6") (pin "2") (pinfunction "K_2") (pintype "passive"))
      (node (ref "L1") (pin "1") (pintype "passive"))
      (node (ref "U5") (pin "6") (pinfunction "SW_6") (pintype "passive"))
    )
    (net (code "60") (name "Net-(D7-K)") (class "Default")
      (node (ref "C23") (pin "2") (pinfunction "2_2") (pintype "passive"))
      (node (ref "D7") (pin "2") (pinfunction "K_2") (pintype "passive"))
      (node (ref "R14") (pin "1") (pinfunction "1_1") (pintype "passive"))
      (node (ref "U5") (pin "5") (pinfunction "IN_5") (pintype "passive"))
    )
    (net (code "61") (name "Net-(U1-BYPASS)") (class "Default")
      (node (ref "C3") (pin "2") (pinfunction "2_2") (pintype "passive"))
      (node (ref "U1") (pin "4") (pinfunction "BYPASS_4") (pintype "passive"))
    )
    (net (code "62") (name "Net-(U5-BS)") (class "Default")
      (node (ref "C18") (pin "2") (pinfunction "2_2") (pintype "passive"))
      (node (ref "C20") (pin "2") (pinfunction "2_2") (pintype "passive"))
      (node (ref "U5") (pin "1") (pinfunction "BS_1") (pintype "passive"))
    )
    (net (code "63") (name "Net-(U5-EN)") (class "Default")
      (node (ref "R14") (pin "2") (pinfunction "2_2") (pintype "passive"))
      (node (ref "U5") (pin "4") (pinfunction "EN_4") (pintype "passive"))
    )
    (net (code "64") (name "Net-(U5-FB)") (class "Default")
      (node (ref "C19") (pin "2") (pinfunction "2_2") (pintype "passive"))
      (node (ref "R10") (pin "1") (pinfunction "1_1") (pintype "passive"))
      (node (ref "R13") (pin "2") (pinfunction "2_2") (pintype "passive"))
      (node (ref "U5") (pin "3") (pinfunction "FB_3") (pintype "passive"))
    )
    (net (code "65") (name "Net-(U6-CATHODE)") (class "Default")
      (node (ref "P3") (pin "1") (pinfunction "1_1") (pintype "passive"))
      (node (ref "R11") (pin "2") (pinfunction "2_2") (pintype "passive"))
      (node (ref "U6") (pin "1") (pinfunction "CATHODE_1") (pintype "passive"))
      (node (ref "U6") (pin "2") (pinfunction "REF_2") (pintype "passive"))
    )
    (net (code "66") (name "Net-(U7A-PD0-OSC_IN)") (class "Default")
      (node (ref "U7") (pin "5") (pinfunction "PD0-OSC_IN_5") (pintype "bidirectional"))
      (node (ref "Y1") (pin "3") (pinfunction "3_3") (pintype "passive"))
    )
    (net (code "67") (name "Net-(U7A-PD1-OSC_OUT)") (class "Default")
      (node (ref "U7") (pin "6") (pinfunction "PD1-OSC_OUT_6") (pintype "bidirectional"))
      (node (ref "Y1") (pin "1") (pinfunction "1_1") (pintype "passive"))
    )
    (net (code "68") (name "Net-(U8-CPH)") (class "Default")
      (node (ref "C24") (pin "2") (pinfunction "2_2") (pintype "passive"))
      (node (ref "U8") (pin "2") (pinfunction "CPH_2") (pintype "power_in"))
    )
    (net (code "69") (name "Net-(U8-CPL)") (class "Default")
      (node (ref "C24") (pin "1") (pinfunction "1_1") (pintype "passive"))
      (node (ref "U8") (pin "1") (pinfunction "CPL_1") (pintype "power_in"))
    )
    (net (code "70") (name "Net-(U8-VCP)") (class "Default")
      (node (ref "C29") (pin "1") (pinfunction "1_1") (pintype "passive"))
      (node (ref "U8") (pin "3") (pinfunction "VCP_3") (pintype "power_in"))
    )
    (net (code "71") (name "Net-(USB1-CC1)") (class "Default")
      (node (ref "R5") (pin "1") (pinfunction "1_1") (pintype "passive"))
      (node (ref "USB1") (pin "A5") (pinfunction "CC1_A5") (pintype "passive"))
    )
    (net (code "72") (name "Net-(USB1-CC2)") (class "Default")
      (node (ref "R6") (pin "1") (pinfunction "1_1") (pintype "passive"))
      (node (ref "USB1") (pin "B5") (pinfunction "CC2_B5") (pintype "passive"))
    )
    (net (code "73") (name "VBUS") (class "Default")
      (node (ref "D5") (pin "1") (pinfunction "A_1") (pintype "passive"))
      (node (ref "R25") (pin "2") (pinfunction "2_2") (pintype "passive"))
      (node (ref "USB1") (pin "A4") (pinfunction "VBUS_A4") (pintype "passive"))
      (node (ref "USB1") (pin "A9") (pinfunction "VBUS_A9") (pintype "passive"))
      (node (ref "USB1") (pin "B4") (pinfunction "VBUS_B4") (pintype "passive"))
      (node (ref "USB1") (pin "B9") (pinfunction "VBUS_B9") (pintype "passive"))
    )
    (net (code "74") (name "VCC") (class "Default")
      (node (ref "C11") (pin "2") (pinfunction "2_2") (pintype "passive"))
      (node (ref "C12") (pin "2") (pinfunction "2_2") (pintype "passive"))
      (node (ref "C13") (pin "2") (pinfunction "2_2") (pintype "passive"))
      (node (ref "C14") (pin "2") (pinfunction "2_2") (pintype "passive"))
      (node (ref "C15") (pin "2") (pinfunction "2_2") (pintype "passive"))
      (node (ref "C29") (pin "2") (pinfunction "2_2") (pintype "passive"))
      (node (ref "D2") (pin "2") (pinfunction "K_2") (pintype "passive"))
      (node (ref "D4") (pin "2") (pinfunction "2_2") (pintype "passive"))
      (node (ref "D7") (pin "1") (pinfunction "A_1") (pintype "passive"))
      (node (ref "U8") (pin "11") (pinfunction "VM2_11") (pintype "power_in"))
      (node (ref "U8") (pin "4") (pinfunction "VM1_4") (pintype "power_in"))
    )
    (net (code "75") (name "VCC_IN") (class "Default")
      (node (ref "D2") (pin "1") (pinfunction "A_1") (pintype "passive"))
    )
    (net (code "76") (name "unconnected-(1-VBREF-Pad6)") (class "Default")
      (node (ref "1") (pin "6") (pinfunction "VBREF_6") (pintype "passive"))
    )
    (net (code "77") (name "unconnected-(U4-NC-Pad5)") (class "Default")
      (node (ref "U4") (pin "5") (pinfunction "NC_5") (pintype "passive"))
    )
    (net (code "78") (name "unconnected-(U4-NC-Pad8)") (class "Default")
      (node (ref "U4") (pin "8") (pinfunction "NC_8") (pintype "passive"))
    )
    (net (code "79") (name "unconnected-(U7A-PC15-OSC32_OUT-Pad4)") (class "Default")
      (node (ref "U7") (pin "4") (pinfunction "PC15-OSC32_OUT_4") (pintype "bidirectional"))
    )
    (net (code "80") (name "unconnected-(USB1-RX1+-PadB11)") (class "Default")
      (node (ref "USB1") (pin "B11") (pinfunction "RX1+_B11") (pintype "passive"))
    )
    (net (code "81") (name "unconnected-(USB1-RX1--PadB10)") (class "Default")
      (node (ref "USB1") (pin "B10") (pinfunction "RX1-_B10") (pintype "passive"))
    )
    (net (code "82") (name "unconnected-(USB1-RX2+-PadA11)") (class "Default")
      (node (ref "USB1") (pin "A11") (pinfunction "RX2+_A11") (pintype "passive"))
    )
    (net (code "83") (name "unconnected-(USB1-RX2--PadA10)") (class "Default")
      (node (ref "USB1") (pin "A10") (pinfunction "RX2-_A10") (pintype "passive"))
    )
    (net (code "84") (name "unconnected-(USB1-SBU1-PadA8)") (class "Default")
      (node (ref "USB1") (pin "A8") (pinfunction "SBU1_A8") (pintype "passive"))
    )
    (net (code "85") (name "unconnected-(USB1-SBU2-PadB8)") (class "Default")
      (node (ref "USB1") (pin "B8") (pinfunction "SBU2_B8") (pintype "passive"))
    )
    (net (code "86") (name "unconnected-(USB1-TX1+-PadA2)") (class "Default")
      (node (ref "USB1") (pin "A2") (pinfunction "TX1+_A2") (pintype "passive"))
    )
    (net (code "87") (name "unconnected-(USB1-TX1--PadA3)") (class "Default")
      (node (ref "USB1") (pin "A3") (pinfunction "TX1-_A3") (pintype "passive"))
    )
    (net (code "88") (name "unconnected-(USB1-TX2+-PadB2)") (class "Default")
      (node (ref "USB1") (pin "B2") (pinfunction "TX2+_B2") (pintype "passive"))
    )
    (net (code "89") (name "unconnected-(USB1-TX2--PadB3)") (class "Default")
      (node (ref "USB1") (pin "B3") (pinfunction "TX2-_B3") (pintype "passive"))
    )
  )
)
